# XBee-Explorer-Dongle.net
KiCad netlist of a schematic drawn in EAGLE
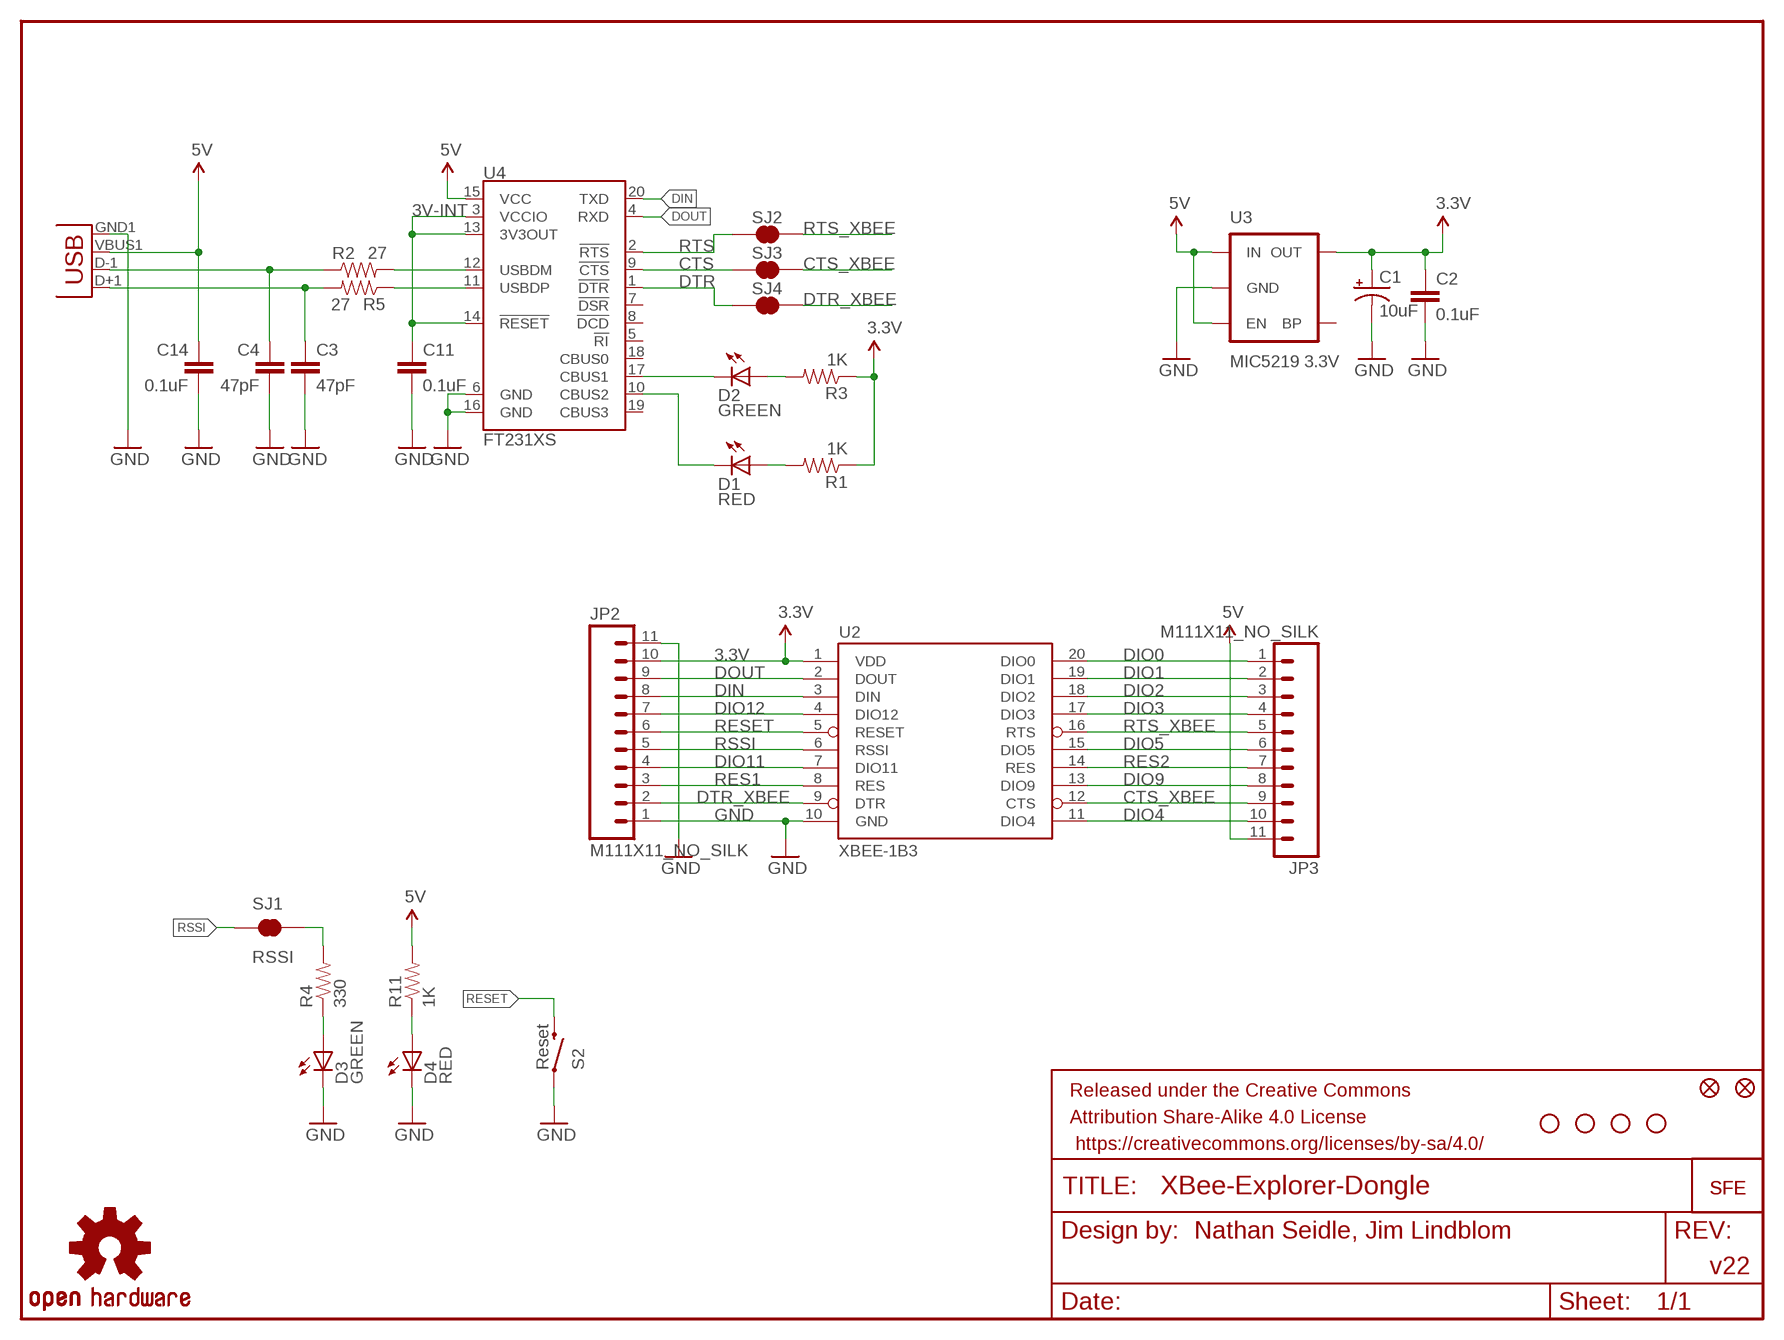
[diagram p0: schematic, sheet 1]

(export (version "E")
  (design (tool "Eeschema 10.0.6"))
  (components
    (comp (ref "C1")
      (value "10uF")
      (footprint "eagle-import:EIA3216")
      (libsource (lib "eagle-import") (part "CAP_POL1206"))
    )
    (comp (ref "C2")
      (value "0.1uF")
      (footprint "eagle-import:0603-CAP")
      (libsource (lib "eagle-import") (part "CAP0603-CAP"))
    )
    (comp (ref "C3")
      (value "47pF")
      (footprint "eagle-import:0603-CAP")
      (libsource (lib "eagle-import") (part "CAP0603-CAP"))
    )
    (comp (ref "C4")
      (value "47pF")
      (footprint "eagle-import:0603-CAP")
      (libsource (lib "eagle-import") (part "CAP0603-CAP"))
    )
    (comp (ref "C11")
      (value "0.1uF")
      (footprint "eagle-import:0603-CAP")
      (libsource (lib "eagle-import") (part "CAP0603-CAP"))
    )
    (comp (ref "C14")
      (value "0.1uF")
      (footprint "eagle-import:0603-CAP")
      (libsource (lib "eagle-import") (part "CAP0603-CAP"))
    )
    (comp (ref "D1")
      (value "RED")
      (footprint "eagle-import:LED-0603")
      (libsource (lib "eagle-import") (part "LED-RED0603"))
    )
    (comp (ref "D2")
      (value "GREEN")
      (footprint "eagle-import:LED-0603")
      (libsource (lib "eagle-import") (part "LED-GREEN0603"))
    )
    (comp (ref "D3")
      (value "GREEN")
      (footprint "eagle-import:LED-0603")
      (libsource (lib "eagle-import") (part "LED-GREEN0603"))
    )
    (comp (ref "D4")
      (value "RED")
      (footprint "eagle-import:LED-0603")
      (libsource (lib "eagle-import") (part "LED-RED0603"))
    )
    (comp (ref "FID1")
      (value "FIDUCIAL1X2")
      (footprint "eagle-import:FIDUCIAL-1X2")
      (libsource (lib "eagle-import") (part "FIDUCIAL1X2"))
    )
    (comp (ref "FID2")
      (value "FIDUCIAL1X2")
      (footprint "eagle-import:FIDUCIAL-1X2")
      (libsource (lib "eagle-import") (part "FIDUCIAL1X2"))
    )
    (comp (ref "FRAME1")
      (value "FRAME-LETTER")
      (footprint "eagle-import:CREATIVE_COMMONS")
      (libsource (lib "eagle-import") (part "FRAME-LETTER"))
    )
    (comp (ref "JP1")
      (value "USBA-SMD-MALE-LOCKING")
      (footprint "eagle-import:USB-A-SMT-MALE-LOCKING")
      (libsource (lib "eagle-import") (part "USBA-SMD-MALE-LOCKING"))
    )
    (comp (ref "JP2")
      (value "M111X11_NO_SILK")
      (footprint "eagle-import:1X11_NO_SILK")
      (libsource (lib "eagle-import") (part "M111X11_NO_SILK"))
    )
    (comp (ref "JP3")
      (value "M111X11_NO_SILK")
      (footprint "eagle-import:1X11_NO_SILK")
      (libsource (lib "eagle-import") (part "M111X11_NO_SILK"))
    )
    (comp (ref "R1")
      (value "1K")
      (footprint "eagle-import:0603-RES")
      (libsource (lib "eagle-import") (part "RESISTOR0603-RES"))
    )
    (comp (ref "R2")
      (value "27")
      (footprint "eagle-import:0603-RES")
      (libsource (lib "eagle-import") (part "RESISTOR0603-RES"))
    )
    (comp (ref "R3")
      (value "1K")
      (footprint "eagle-import:0603-RES")
      (libsource (lib "eagle-import") (part "RESISTOR0603-RES"))
    )
    (comp (ref "R4")
      (value "330")
      (footprint "eagle-import:0603-RES")
      (libsource (lib "eagle-import") (part "RESISTOR0603-RES"))
    )
    (comp (ref "R5")
      (value "27")
      (footprint "eagle-import:0603-RES")
      (libsource (lib "eagle-import") (part "RESISTOR0603-RES"))
    )
    (comp (ref "R11")
      (value "1K")
      (footprint "eagle-import:0603-RES")
      (libsource (lib "eagle-import") (part "RESISTOR0603-RES"))
    )
    (comp (ref "S2")
      (value "Reset")
      (footprint "eagle-import:TACTILE_SWITCH_SMD")
      (libsource (lib "eagle-import") (part "SWITCH-MOMENTARY-2SMD"))
    )
    (comp (ref "SJ1")
      (value "RSSI")
      (footprint "eagle-import:SJ_2S-TRACE")
      (libsource (lib "eagle-import") (part "SOLDERJUMPERTRACE"))
    )
    (comp (ref "SJ2")
      (value "RSSI")
      (footprint "eagle-import:SJ_2S-TRACE")
      (libsource (lib "eagle-import") (part "SOLDERJUMPERTRACE"))
    )
    (comp (ref "SJ3")
      (value "RSSI")
      (footprint "eagle-import:SJ_2S-TRACE")
      (libsource (lib "eagle-import") (part "SOLDERJUMPERTRACE"))
    )
    (comp (ref "SJ4")
      (value "RSSI")
      (footprint "eagle-import:SJ_2S-TRACE")
      (libsource (lib "eagle-import") (part "SOLDERJUMPERTRACE"))
    )
    (comp (ref "U$1")
      (value "LOGO-SFESK")
      (footprint "eagle-import:SFE-LOGO-FLAME")
      (libsource (lib "eagle-import") (part "LOGO-SFESK"))
    )
    (comp (ref "U$4")
      (value "LOGO-SFENEW")
      (footprint "eagle-import:SFE-NEW-WEBLOGO")
      (libsource (lib "eagle-import") (part "LOGO-SFENEW"))
    )
    (comp (ref "U$5")
      (value "STAND-OFF")
      (footprint "eagle-import:STAND-OFF")
      (libsource (lib "eagle-import") (part "STAND-OFF"))
    )
    (comp (ref "U$7")
      (value "OSHW-LOGOS")
      (footprint "eagle-import:OSHW-LOGO-S")
      (libsource (lib "eagle-import") (part "OSHW-LOGOS"))
    )
    (comp (ref "U$9")
      (value "STAND-OFF")
      (footprint "eagle-import:STAND-OFF")
      (libsource (lib "eagle-import") (part "STAND-OFF"))
    )
    (comp (ref "U$10")
      (value "STAND-OFF")
      (footprint "eagle-import:STAND-OFF")
      (libsource (lib "eagle-import") (part "STAND-OFF"))
    )
    (comp (ref "U$11")
      (value "STAND-OFF")
      (footprint "eagle-import:STAND-OFF")
      (libsource (lib "eagle-import") (part "STAND-OFF"))
    )
    (comp (ref "U2")
      (value "XBEE-1B3")
      (footprint "eagle-import:XBEE-SMD")
      (libsource (lib "eagle-import") (part "XBEE-1B3"))
    )
    (comp (ref "U3")
      (value "MIC5219 3.3V")
      (footprint "eagle-import:SOT23-5")
      (libsource (lib "eagle-import") (part "V_REG_LDOSMD"))
    )
    (comp (ref "U4")
      (value "FT231XS")
      (footprint "eagle-import:SSOP20_L")
      (libsource (lib "eagle-import") (part "FT231XS"))
    )
  )
  (nets
    (net (code "1") (name "/3V-INT") (class "Default")
      (node (ref "C11") (pin "1") (pinfunction "1_1") (pintype "passive"))
      (node (ref "U4") (pin "13") (pinfunction "3V3OUT_13") (pintype "bidirectional"))
      (node (ref "U4") (pin "14") (pinfunction "~{RESET}_14") (pintype "bidirectional"))
      (node (ref "U4") (pin "3") (pinfunction "VCCIO_3") (pintype "bidirectional"))
    )
    (net (code "2") (name "/CTS") (class "Default")
      (node (ref "SJ3") (pin "1") (pinfunction "1_1") (pintype "passive"))
      (node (ref "U4") (pin "9") (pinfunction "~{CTS}_9") (pintype "bidirectional"))
    )
    (net (code "3") (name "/CTS_XBEE") (class "Default")
      (node (ref "JP3") (pin "9") (pinfunction "9_9") (pintype "passive"))
      (node (ref "SJ3") (pin "2") (pinfunction "2_2") (pintype "passive"))
      (node (ref "U2") (pin "12") (pinfunction "CTS_12") (pintype "output"))
    )
    (net (code "4") (name "/DIO0") (class "Default")
      (node (ref "JP3") (pin "1") (pinfunction "1_1") (pintype "passive"))
      (node (ref "U2") (pin "20") (pinfunction "DIO0_20") (pintype "bidirectional"))
    )
    (net (code "5") (name "/DIO1") (class "Default")
      (node (ref "JP3") (pin "2") (pinfunction "2_2") (pintype "passive"))
      (node (ref "U2") (pin "19") (pinfunction "DIO1_19") (pintype "bidirectional"))
    )
    (net (code "6") (name "/DIO2") (class "Default")
      (node (ref "JP3") (pin "3") (pinfunction "3_3") (pintype "passive"))
      (node (ref "U2") (pin "18") (pinfunction "DIO2_18") (pintype "bidirectional"))
    )
    (net (code "7") (name "/DIO3") (class "Default")
      (node (ref "JP3") (pin "4") (pinfunction "4_4") (pintype "passive"))
      (node (ref "U2") (pin "17") (pinfunction "DIO3_17") (pintype "bidirectional"))
    )
    (net (code "8") (name "/DIO4") (class "Default")
      (node (ref "JP3") (pin "10") (pinfunction "10_10") (pintype "passive"))
      (node (ref "U2") (pin "11") (pinfunction "DIO4_11") (pintype "bidirectional"))
    )
    (net (code "9") (name "/DIO5") (class "Default")
      (node (ref "JP3") (pin "6") (pinfunction "6_6") (pintype "passive"))
      (node (ref "U2") (pin "15") (pinfunction "DIO5_15") (pintype "bidirectional"))
    )
    (net (code "10") (name "/DIO9") (class "Default")
      (node (ref "JP3") (pin "8") (pinfunction "8_8") (pintype "passive"))
      (node (ref "U2") (pin "13") (pinfunction "DIO9_13") (pintype "bidirectional"))
    )
    (net (code "11") (name "/DIO11") (class "Default")
      (node (ref "JP2") (pin "4") (pinfunction "4_4") (pintype "passive"))
      (node (ref "U2") (pin "7") (pinfunction "DIO11_7") (pintype "bidirectional"))
    )
    (net (code "12") (name "/DIO12") (class "Default")
      (node (ref "JP2") (pin "7") (pinfunction "7_7") (pintype "passive"))
      (node (ref "U2") (pin "4") (pinfunction "DIO12_4") (pintype "bidirectional"))
    )
    (net (code "13") (name "/DTR") (class "Default")
      (node (ref "SJ4") (pin "1") (pinfunction "1_1") (pintype "passive"))
      (node (ref "U4") (pin "1") (pinfunction "~{DTR}_1") (pintype "bidirectional"))
    )
    (net (code "14") (name "/DTR_XBEE") (class "Default")
      (node (ref "JP2") (pin "2") (pinfunction "2_2") (pintype "passive"))
      (node (ref "SJ4") (pin "2") (pinfunction "2_2") (pintype "passive"))
      (node (ref "U2") (pin "9") (pinfunction "DTR_9") (pintype "bidirectional"))
    )
    (net (code "15") (name "/RES1") (class "Default")
      (node (ref "JP2") (pin "3") (pinfunction "3_3") (pintype "passive"))
      (node (ref "U2") (pin "8") (pinfunction "RES_8") (pintype "bidirectional"))
    )
    (net (code "16") (name "/RES2") (class "Default")
      (node (ref "JP3") (pin "7") (pinfunction "7_7") (pintype "passive"))
      (node (ref "U2") (pin "14") (pinfunction "RES_14") (pintype "bidirectional"))
    )
    (net (code "17") (name "/RTS") (class "Default")
      (node (ref "SJ2") (pin "1") (pinfunction "1_1") (pintype "passive"))
      (node (ref "U4") (pin "2") (pinfunction "~{RTS}_2") (pintype "bidirectional"))
    )
    (net (code "18") (name "/RTS_XBEE") (class "Default")
      (node (ref "JP3") (pin "5") (pinfunction "5_5") (pintype "passive"))
      (node (ref "SJ2") (pin "2") (pinfunction "2_2") (pintype "passive"))
      (node (ref "U2") (pin "16") (pinfunction "RTS_16") (pintype "input"))
    )
    (net (code "19") (name "3.3V") (class "Default")
      (node (ref "C1") (pin "A") (pinfunction "+_A") (pintype "passive"))
      (node (ref "C2") (pin "1") (pinfunction "1_1") (pintype "passive"))
      (node (ref "JP2") (pin "10") (pinfunction "10_10") (pintype "passive"))
      (node (ref "R1") (pin "1") (pinfunction "1_1") (pintype "passive"))
      (node (ref "R3") (pin "1") (pinfunction "1_1") (pintype "passive"))
      (node (ref "U2") (pin "1") (pinfunction "VDD_1") (pintype "power_in"))
      (node (ref "U3") (pin "5") (pinfunction "OUT_5") (pintype "passive"))
    )
    (net (code "20") (name "5V") (class "Default")
      (node (ref "C14") (pin "1") (pinfunction "1_1") (pintype "passive"))
      (node (ref "JP1") (pin "VBUS1") (pinfunction "VBUS_VBUS1") (pintype "bidirectional"))
      (node (ref "JP3") (pin "11") (pinfunction "11_11") (pintype "passive"))
      (node (ref "R11") (pin "2") (pinfunction "2_2") (pintype "passive"))
      (node (ref "U3") (pin "1") (pinfunction "IN_1") (pintype "input"))
      (node (ref "U3") (pin "3") (pinfunction "EN_3") (pintype "input"))
      (node (ref "U4") (pin "15") (pinfunction "VCC_15") (pintype "bidirectional"))
    )
    (net (code "21") (name "DIN") (class "Default")
      (node (ref "JP2") (pin "8") (pinfunction "8_8") (pintype "passive"))
      (node (ref "U2") (pin "3") (pinfunction "DIN_3") (pintype "input"))
      (node (ref "U4") (pin "20") (pinfunction "TXD_20") (pintype "bidirectional"))
    )
    (net (code "22") (name "DOUT") (class "Default")
      (node (ref "JP2") (pin "9") (pinfunction "9_9") (pintype "passive"))
      (node (ref "U2") (pin "2") (pinfunction "DOUT_2") (pintype "output"))
      (node (ref "U4") (pin "4") (pinfunction "RXD_4") (pintype "bidirectional"))
    )
    (net (code "23") (name "GND") (class "Default")
      (node (ref "C1") (pin "C") (pinfunction "-_C") (pintype "passive"))
      (node (ref "C11") (pin "2") (pinfunction "2_2") (pintype "passive"))
      (node (ref "C14") (pin "2") (pinfunction "2_2") (pintype "passive"))
      (node (ref "C2") (pin "2") (pinfunction "2_2") (pintype "passive"))
      (node (ref "C3") (pin "2") (pinfunction "2_2") (pintype "passive"))
      (node (ref "C4") (pin "2") (pinfunction "2_2") (pintype "passive"))
      (node (ref "D3") (pin "C") (pinfunction "C_C") (pintype "passive"))
      (node (ref "D4") (pin "C") (pinfunction "C_C") (pintype "passive"))
      (node (ref "JP1") (pin "GND1") (pinfunction "GND_GND1") (pintype "bidirectional"))
      (node (ref "JP2") (pin "1") (pinfunction "1_1") (pintype "passive"))
      (node (ref "JP2") (pin "11") (pinfunction "11_11") (pintype "passive"))
      (node (ref "S2") (pin "1") (pinfunction "1_1") (pintype "passive"))
      (node (ref "U2") (pin "10") (pinfunction "GND_10") (pintype "power_in"))
      (node (ref "U3") (pin "2") (pinfunction "GND_2") (pintype "input"))
      (node (ref "U4") (pin "16") (pinfunction "GND_16") (pintype "bidirectional"))
      (node (ref "U4") (pin "6") (pinfunction "GND_6") (pintype "bidirectional"))
    )
    (net (code "24") (name "Net-(D1-PadA)") (class "Default")
      (node (ref "D1") (pin "A") (pinfunction "A_A") (pintype "passive"))
      (node (ref "R1") (pin "2") (pinfunction "2_2") (pintype "passive"))
    )
    (net (code "25") (name "Net-(D2-PadA)") (class "Default")
      (node (ref "D2") (pin "A") (pinfunction "A_A") (pintype "passive"))
      (node (ref "R3") (pin "2") (pinfunction "2_2") (pintype "passive"))
    )
    (net (code "26") (name "Net-(D3-PadA)") (class "Default")
      (node (ref "D3") (pin "A") (pinfunction "A_A") (pintype "passive"))
      (node (ref "R4") (pin "1") (pinfunction "1_1") (pintype "passive"))
    )
    (net (code "27") (name "Net-(D4-PadA)") (class "Default")
      (node (ref "D4") (pin "A") (pinfunction "A_A") (pintype "passive"))
      (node (ref "R11") (pin "1") (pinfunction "1_1") (pintype "passive"))
    )
    (net (code "28") (name "Net-(JP1-D+)") (class "Default")
      (node (ref "C3") (pin "1") (pinfunction "1_1") (pintype "passive"))
      (node (ref "JP1") (pin "D+1") (pinfunction "D+_D+1") (pintype "bidirectional"))
      (node (ref "R5") (pin "2") (pinfunction "2_2") (pintype "passive"))
    )
    (net (code "29") (name "Net-(JP1-D-)") (class "Default")
      (node (ref "C4") (pin "1") (pinfunction "1_1") (pintype "passive"))
      (node (ref "JP1") (pin "D-1") (pinfunction "D-_D-1") (pintype "bidirectional"))
      (node (ref "R2") (pin "1") (pinfunction "1_1") (pintype "passive"))
    )
    (net (code "30") (name "Net-(R4-Pad2)") (class "Default")
      (node (ref "R4") (pin "2") (pinfunction "2_2") (pintype "passive"))
      (node (ref "SJ1") (pin "2") (pinfunction "2_2") (pintype "passive"))
    )
    (net (code "31") (name "Net-(U4-CBUS1)") (class "Default")
      (node (ref "D2") (pin "C") (pinfunction "C_C") (pintype "passive"))
      (node (ref "U4") (pin "17") (pinfunction "CBUS1_17") (pintype "bidirectional"))
    )
    (net (code "32") (name "Net-(U4-CBUS2)") (class "Default")
      (node (ref "D1") (pin "C") (pinfunction "C_C") (pintype "passive"))
      (node (ref "U4") (pin "10") (pinfunction "CBUS2_10") (pintype "bidirectional"))
    )
    (net (code "33") (name "Net-(U4-USBDM)") (class "Default")
      (node (ref "R2") (pin "2") (pinfunction "2_2") (pintype "passive"))
      (node (ref "U4") (pin "12") (pinfunction "USBDM_12") (pintype "bidirectional"))
    )
    (net (code "34") (name "Net-(U4-USBDP)") (class "Default")
      (node (ref "R5") (pin "1") (pinfunction "1_1") (pintype "passive"))
      (node (ref "U4") (pin "11") (pinfunction "USBDP_11") (pintype "bidirectional"))
    )
    (net (code "35") (name "RESET") (class "Default")
      (node (ref "JP2") (pin "6") (pinfunction "6_6") (pintype "passive"))
      (node (ref "S2") (pin "3") (pinfunction "2_3") (pintype "passive"))
      (node (ref "U2") (pin "5") (pinfunction "RESET_5") (pintype "input"))
    )
    (net (code "36") (name "RSSI") (class "Default")
      (node (ref "JP2") (pin "5") (pinfunction "5_5") (pintype "passive"))
      (node (ref "SJ1") (pin "1") (pinfunction "1_1") (pintype "passive"))
      (node (ref "U2") (pin "6") (pinfunction "RSSI_6") (pintype "bidirectional"))
    )
    (net (code "37") (name "unconnected-(U3-BP-Pad4)") (class "Default")
      (node (ref "U3") (pin "4") (pinfunction "BP_4") (pintype "input"))
    )
    (net (code "38") (name "unconnected-(U4-CBUS0-Pad18)") (class "Default")
      (node (ref "U4") (pin "18") (pinfunction "CBUS0_18") (pintype "bidirectional"))
    )
    (net (code "39") (name "unconnected-(U4-CBUS3-Pad19)") (class "Default")
      (node (ref "U4") (pin "19") (pinfunction "CBUS3_19") (pintype "bidirectional"))
    )
    (net (code "40") (name "unconnected-(U4-~{DCD}-Pad8)") (class "Default")
      (node (ref "U4") (pin "8") (pinfunction "~{DCD}_8") (pintype "bidirectional"))
    )
    (net (code "41") (name "unconnected-(U4-~{DSR}-Pad7)") (class "Default")
      (node (ref "U4") (pin "7") (pinfunction "~{DSR}_7") (pintype "bidirectional"))
    )
    (net (code "42") (name "unconnected-(U4-~{RI}-Pad5)") (class "Default")
      (node (ref "U4") (pin "5") (pinfunction "~{RI}_5") (pintype "bidirectional"))
    )
  )
)
